# buck_boost.net
KiCad netlist of a schematic drawn in Altium Designer
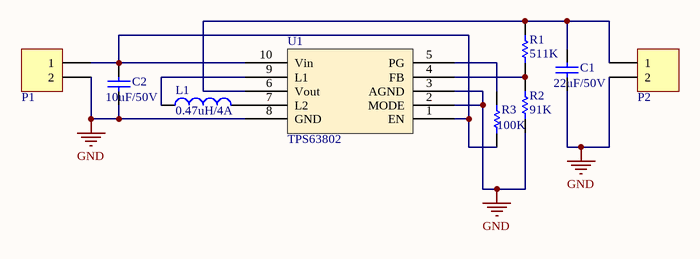
[diagram p0: buck&boost.SchDoc]

(export (version "E")
  (design (tool "Eeschema 10.0.6"))
  (components
    (comp (ref "C1")
      (value "22uF/50V")
      (footprint "CAP-SM-0805")
      (description "Capacitor")
      (fields (field (name "Comment") "Cap Non-Pol SMD"))
      (libsource (lib "PIF_Library") (part "Cap Non-Pol SMD"))
    )
    (comp (ref "C2")
      (value "10uF/50V")
      (footprint "CAP-SM-0805")
      (description "Capacitor")
      (fields (field (name "Comment") "Cap Non-Pol SMD"))
      (libsource (lib "PIF_Library") (part "Cap Non-Pol SMD"))
    )
    (comp (ref "L1")
      (value "0.47uH/4A")
      (footprint "INDUCTOR 12.5x12.5")
      (description "Inductor")
      (libsource (lib "PIF_Library") (part "Inductor"))
    )
    (comp (ref "P1")
      (value "Header 2")
      (footprint "JP2")
      (description "Header, 2-Pin")
      (fields (field (name "PUBLISHER") "Altium Limited"))
      (libsource (lib "PIF_Library") (part "Header 2"))
    )
    (comp (ref "P2")
      (value "Header 2")
      (footprint "JP2")
      (description "Header, 2-Pin")
      (fields (field (name "PUBLISHER") "Altium Limited"))
      (libsource (lib "") (part "Header 2_1"))
    )
    (comp (ref "R1")
      (value "511K")
      (footprint "RES-SM-0603")
      (description "Resistor")
      (fields (field (name "Comment") "RESISTOR SMD"))
      (libsource (lib "PIF_Library") (part "RESISTOR SMD"))
    )
    (comp (ref "R2")
      (value "91K")
      (footprint "RES-SM-0603")
      (description "Resistor")
      (fields (field (name "Comment") "RESISTOR SMD"))
      (libsource (lib "PIF_Library") (part "RESISTOR SMD"))
    )
    (comp (ref "R3")
      (value "100K")
      (footprint "RES-SM-0603")
      (description "Resistor")
      (fields (field (name "Comment") "RESISTOR SMD"))
      (libsource (lib "PIF_Library") (part "RESISTOR SMD"))
    )
    (comp (ref "U1")
      (value "TPS63802")
      (footprint "TPS63802")
      (description "SMD")
      (libsource (lib "buck&boost") (part "TPS63802"))
    )
  )
  (nets
    (net (code "1") (name "GND") (class "Default")
      (node (ref "C1") (pin "1") (pinfunction "1_1") (pintype "passive"))
      (node (ref "C2") (pin "1") (pinfunction "1_1") (pintype "passive"))
      (node (ref "P1") (pin "2") (pinfunction "2_2") (pintype "passive"))
      (node (ref "P2") (pin "2") (pinfunction "2_2") (pintype "passive"))
      (node (ref "R2") (pin "1") (pinfunction "1_1") (pintype "passive"))
      (node (ref "U1") (pin "2") (pinfunction "MODE_2") (pintype "passive"))
      (node (ref "U1") (pin "3") (pinfunction "AGND_3") (pintype "passive"))
      (node (ref "U1") (pin "8") (pinfunction "GND_8") (pintype "passive"))
    )
    (net (code "2") (name "Net-(U1-EN)") (class "Default")
      (node (ref "C2") (pin "2") (pinfunction "2_2") (pintype "passive"))
      (node (ref "P1") (pin "1") (pinfunction "1_1") (pintype "passive"))
      (node (ref "R3") (pin "1") (pinfunction "1_1") (pintype "passive"))
      (node (ref "U1") (pin "1") (pinfunction "EN_1") (pintype "passive"))
      (node (ref "U1") (pin "10") (pinfunction "Vin_10") (pintype "passive"))
    )
    (net (code "3") (name "Net-(U1-FB)") (class "Default")
      (node (ref "R1") (pin "1") (pinfunction "1_1") (pintype "passive"))
      (node (ref "R2") (pin "2") (pinfunction "2_2") (pintype "passive"))
      (node (ref "U1") (pin "4") (pinfunction "FB_4") (pintype "passive"))
    )
    (net (code "4") (name "Net-(U1-L1)") (class "Default")
      (node (ref "L1") (pin "1") (pinfunction "1_1") (pintype "passive"))
      (node (ref "U1") (pin "9") (pinfunction "L1_9") (pintype "passive"))
    )
    (net (code "5") (name "Net-(U1-L2)") (class "Default")
      (node (ref "L1") (pin "2") (pinfunction "2_2") (pintype "passive"))
      (node (ref "U1") (pin "7") (pinfunction "L2_7") (pintype "passive"))
    )
    (net (code "6") (name "Net-(U1-PG)") (class "Default")
      (node (ref "R3") (pin "2") (pinfunction "2_2") (pintype "passive"))
      (node (ref "U1") (pin "5") (pinfunction "PG_5") (pintype "passive"))
    )
    (net (code "7") (name "Net-(U1-Vout)") (class "Default")
      (node (ref "C1") (pin "2") (pinfunction "2_2") (pintype "passive"))
      (node (ref "P2") (pin "1") (pinfunction "1_1") (pintype "passive"))
      (node (ref "R1") (pin "2") (pinfunction "2_2") (pintype "passive"))
      (node (ref "U1") (pin "6") (pinfunction "Vout_6") (pintype "passive"))
    )
  )
)
